# Intelligent_7-Segment_Display.net
KiCad netlist of a schematic drawn in EasyEDA
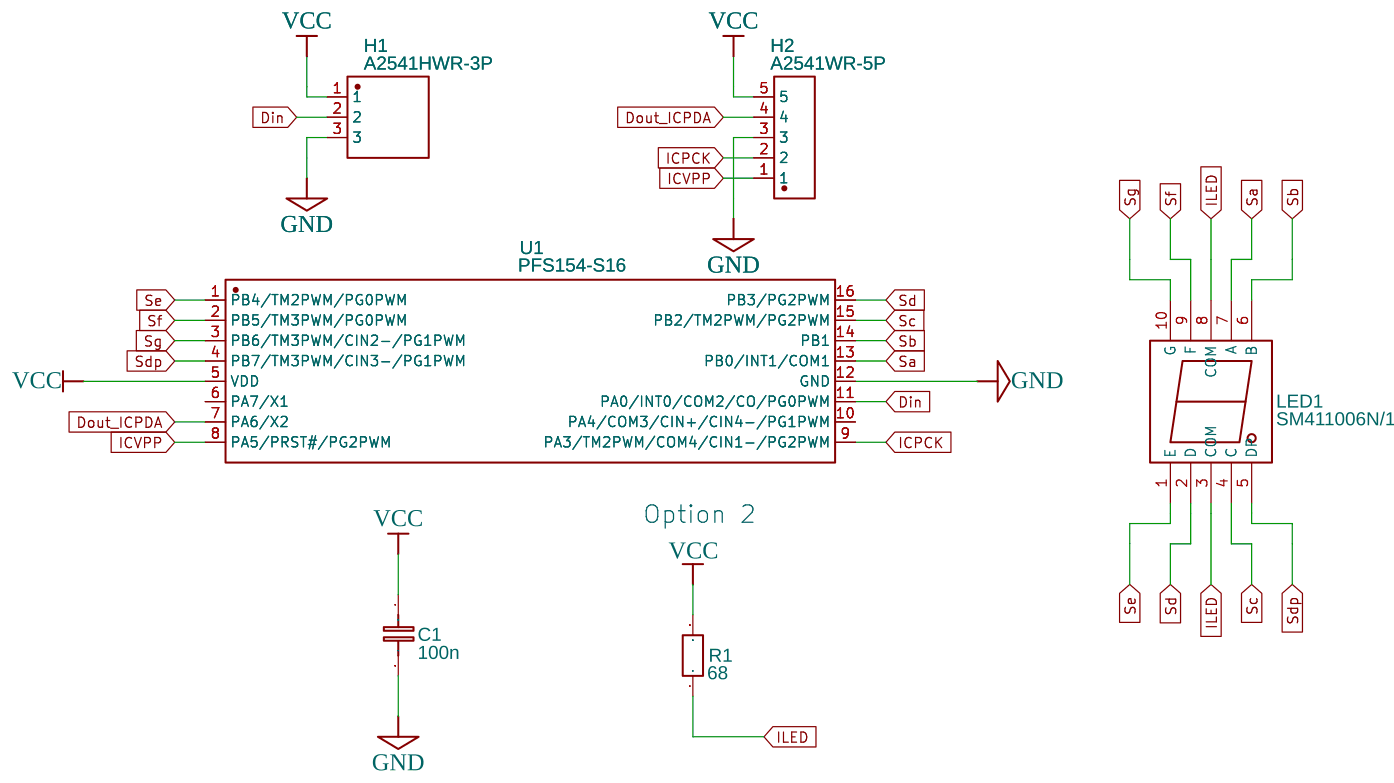
[diagram p0: schematic sheet]

(export (version "E")
  (design (tool "Eeschema 10.0.6"))
  (components
    (comp (ref "C1") (value "100n") (libsource (lib "") (part "Cap_0805_EU")))
    (comp (ref "H1")
      (value "A2541HWR-3P")
      (fields (field (name "BOM_Supplier Part") "C225511"))
      (libsource (lib "") (part "A2541HWR-3P"))
    )
    (comp (ref "H2")
      (value "A2541WR-5P")
      (fields (field (name "BOM_Supplier Part") "C225491"))
      (libsource (lib "") (part "A2541WR-5P"))
    )
    (comp (ref "LED1")
      (value "SM411006N/15")
      (fields (field (name "BOM_Supplier Part") "C252204"))
      (libsource (lib "") (part "SM411006N/15"))
    )
    (comp (ref "R1") (value "68") (libsource (lib "") (part "Res_0805(1/8W)_EU")))
    (comp (ref "U1")
      (value "PFS154-S16")
      (fields (field (name "BOM_Supplier Part") "C317613"))
      (libsource (lib "") (part "PFS154-S16"))
    )
  )
  (nets
    (net (code "1") (name "Din") (class "Default")
      (node (ref "H1") (pin "2") (pinfunction "2_2") (pintype "unspecified"))
      (node (ref "U1") (pin "11") (pinfunction "PA0/INT0/COM2/CO/PG0PWM_11") (pintype "unspecified"))
    )
    (net (code "2") (name "Dout_ICPDA") (class "Default")
      (node (ref "H2") (pin "4") (pinfunction "4_4") (pintype "unspecified"))
      (node (ref "U1") (pin "7") (pinfunction "PA6/X2_7") (pintype "unspecified"))
    )
    (net (code "3") (name "GND") (class "Default")
      (node (ref "C1") (pin "2") (pinfunction "2_2") (pintype "unspecified"))
      (node (ref "H1") (pin "3") (pinfunction "3_3") (pintype "unspecified"))
      (node (ref "H2") (pin "3") (pinfunction "3_3") (pintype "unspecified"))
      (node (ref "U1") (pin "12") (pinfunction "GND_12") (pintype "unspecified"))
    )
    (net (code "4") (name "ICPCK") (class "Default")
      (node (ref "H2") (pin "2") (pinfunction "2_2") (pintype "unspecified"))
      (node (ref "U1") (pin "9") (pinfunction "PA3/TM2PWM/COM4/CIN1-/PG2PWM_9") (pintype "unspecified"))
    )
    (net (code "5") (name "ICVPP") (class "Default")
      (node (ref "H2") (pin "1") (pinfunction "1_1") (pintype "unspecified"))
      (node (ref "U1") (pin "8") (pinfunction "PA5/PRST#/PG2PWM_8") (pintype "unspecified"))
    )
    (net (code "6") (name "ILED") (class "Default")
      (node (ref "LED1") (pin "3") (pinfunction "COM_3") (pintype "unspecified"))
      (node (ref "LED1") (pin "8") (pinfunction "COM_8") (pintype "unspecified"))
      (node (ref "R1") (pin "1") (pinfunction "1_1") (pintype "unspecified"))
    )
    (net (code "7") (name "Sa") (class "Default")
      (node (ref "LED1") (pin "7") (pinfunction "A_7") (pintype "unspecified"))
      (node (ref "U1") (pin "13") (pinfunction "PB0/INT1/COM1_13") (pintype "unspecified"))
    )
    (net (code "8") (name "Sb") (class "Default")
      (node (ref "LED1") (pin "6") (pinfunction "B_6") (pintype "unspecified"))
      (node (ref "U1") (pin "14") (pinfunction "PB1_14") (pintype "unspecified"))
    )
    (net (code "9") (name "Sc") (class "Default")
      (node (ref "LED1") (pin "4") (pinfunction "C_4") (pintype "unspecified"))
      (node (ref "U1") (pin "15") (pinfunction "PB2/TM2PWM/PG2PWM_15") (pintype "unspecified"))
    )
    (net (code "10") (name "Sd") (class "Default")
      (node (ref "LED1") (pin "2") (pinfunction "D_2") (pintype "unspecified"))
      (node (ref "U1") (pin "16") (pinfunction "PB3/PG2PWM_16") (pintype "unspecified"))
    )
    (net (code "11") (name "Sdp") (class "Default")
      (node (ref "LED1") (pin "5") (pinfunction "DP_5") (pintype "unspecified"))
      (node (ref "U1") (pin "4") (pinfunction "PB7/TM3PWM/CIN3-/PG1PWM_4") (pintype "unspecified"))
    )
    (net (code "12") (name "Se") (class "Default")
      (node (ref "LED1") (pin "1") (pinfunction "E_1") (pintype "unspecified"))
      (node (ref "U1") (pin "1") (pinfunction "PB4/TM2PWM/PG0PWM_1") (pintype "unspecified"))
    )
    (net (code "13") (name "Sf") (class "Default")
      (node (ref "LED1") (pin "9") (pinfunction "F_9") (pintype "unspecified"))
      (node (ref "U1") (pin "2") (pinfunction "PB5/TM3PWM/PG0PWM_2") (pintype "unspecified"))
    )
    (net (code "14") (name "Sg") (class "Default")
      (node (ref "LED1") (pin "10") (pinfunction "G_10") (pintype "unspecified"))
      (node (ref "U1") (pin "3") (pinfunction "PB6/TM3PWM/CIN2-/PG1PWM_3") (pintype "unspecified"))
    )
    (net (code "15") (name "VCC") (class "Default")
      (node (ref "C1") (pin "1") (pinfunction "1_1") (pintype "unspecified"))
      (node (ref "H1") (pin "1") (pinfunction "1_1") (pintype "unspecified"))
      (node (ref "H2") (pin "5") (pinfunction "5_5") (pintype "unspecified"))
      (node (ref "R1") (pin "2") (pinfunction "2_2") (pintype "unspecified"))
      (node (ref "U1") (pin "5") (pinfunction "VDD_5") (pintype "unspecified"))
    )
    (net (code "16") (name "unconnected-(U1-PA4{slash}COM3{slash}CIN+{slash}CIN4-{slash}PG1PWM-Pad10)") (class "Default")
      (node (ref "U1") (pin "10") (pinfunction "PA4/COM3/CIN+/CIN4-/PG1PWM_10") (pintype "unspecified"))
    )
    (net (code "17") (name "unconnected-(U1-PA7{slash}X1-Pad6)") (class "Default")
      (node (ref "U1") (pin "6") (pinfunction "PA7/X1_6") (pintype "unspecified"))
    )
  )
)
